# Sheet1.net
KiCad netlist of a schematic drawn in Altium Designer
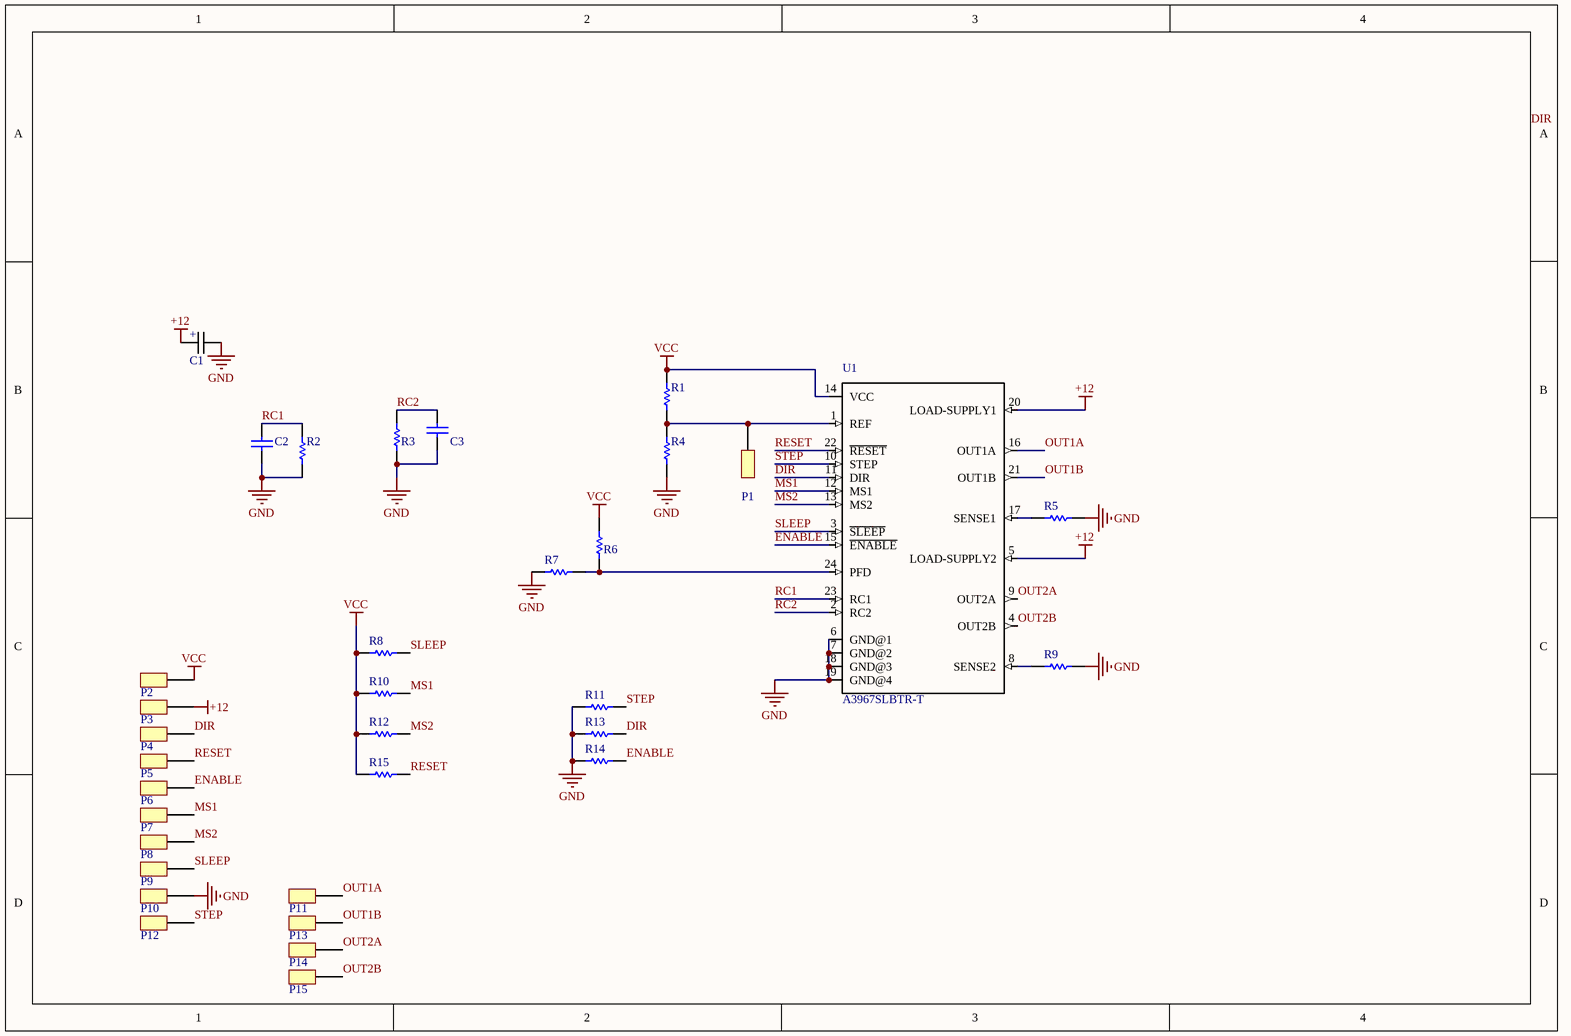
[diagram p0: Sheet1.SchDoc]

(export (version "E")
  (design (tool "Eeschema 10.0.6"))
  (components
    (comp (ref "C1") (value "~") (footprint "CAP 865080342006") (libsource (lib "SolarCar") (part "CAP")))
    (comp (ref "C2")
      (value "CAP 680pF 16V 0603(1608)")
      (footprint "CAPC0603(1608)100_M")
      (description "CAP 680pF 16V ±10% 0603 (1608 Metric) Thickness 1mm SMD")
      (fields (field (name "TOLERANCE") "Â±10%"))
      (libsource (lib "Altium Content Vault") (part "CAP"))
    )
    (comp (ref "C3")
      (value "CAP 680pF 16V 0603(1608)")
      (footprint "CAPC0603(1608)100_M")
      (description "CAP 680pF 16V ±10% 0603 (1608 Metric) Thickness 1mm SMD")
      (fields (field (name "TOLERANCE") "Â±10%"))
      (libsource (lib "Altium Content Vault") (part "CAP"))
    )
    (comp (ref "P1") (value "Pin 100mil") (footprint "Pin 100mil") (libsource (lib "") (part "1-Pin_1")))
    (comp (ref "P2")
      (value "Pin 100mil")
      (footprint "Pin 100mil")
      (libsource (lib "SolarCar") (part "1-Pin"))
    )
    (comp (ref "P3")
      (value "Pin 100mil")
      (footprint "Pin 100mil")
      (libsource (lib "SolarCar") (part "1-Pin"))
    )
    (comp (ref "P4")
      (value "Pin 100mil")
      (footprint "Pin 100mil")
      (libsource (lib "SolarCar") (part "1-Pin"))
    )
    (comp (ref "P5")
      (value "Pin 100mil")
      (footprint "Pin 100mil")
      (libsource (lib "SolarCar") (part "1-Pin"))
    )
    (comp (ref "P6")
      (value "Pin 100mil")
      (footprint "Pin 100mil")
      (libsource (lib "SolarCar") (part "1-Pin"))
    )
    (comp (ref "P7")
      (value "Pin 100mil")
      (footprint "Pin 100mil")
      (libsource (lib "SolarCar") (part "1-Pin"))
    )
    (comp (ref "P8")
      (value "Pin 100mil")
      (footprint "Pin 100mil")
      (libsource (lib "SolarCar") (part "1-Pin"))
    )
    (comp (ref "P9")
      (value "Pin 100mil")
      (footprint "Pin 100mil")
      (libsource (lib "SolarCar") (part "1-Pin"))
    )
    (comp (ref "P10")
      (value "Pin 100mil")
      (footprint "Pin 100mil")
      (libsource (lib "SolarCar") (part "1-Pin"))
    )
    (comp (ref "P11")
      (value "Pin 100mil")
      (footprint "Pin 100mil")
      (libsource (lib "SolarCar") (part "1-Pin"))
    )
    (comp (ref "P12")
      (value "Pin 100mil")
      (footprint "Pin 100mil")
      (libsource (lib "SolarCar") (part "1-Pin"))
    )
    (comp (ref "P13")
      (value "Pin 100mil")
      (footprint "Pin 100mil")
      (libsource (lib "SolarCar") (part "1-Pin"))
    )
    (comp (ref "P14")
      (value "Pin 100mil")
      (footprint "Pin 100mil")
      (libsource (lib "SolarCar") (part "1-Pin"))
    )
    (comp (ref "P15")
      (value "Pin 100mil")
      (footprint "Pin 100mil")
      (libsource (lib "SolarCar") (part "1-Pin"))
    )
    (comp (ref "R1")
      (value "6K04 1% 0603(1608)")
      (footprint "RESC0603(1608)_M")
      (description "6K04 0.1W 1% 0603 (1608 Metric)  SMD")
      (fields (field (name "TOLERANCE") "1 %") (field (name "POWER") "0.1 W"))
      (libsource (lib "Altium Content Vault") (part "RES"))
    )
    (comp (ref "R2")
      (value "20K 5% 0603(1608)")
      (footprint "RESC0603(1608)_N")
      (description "20K 0.1W 5% 0603 (1608 Metric)  SMD")
      (fields (field (name "TOLERANCE") "5 %") (field (name "POWER") "0.1 W"))
      (libsource (lib "Altium Content Vault") (part "RES"))
    )
    (comp (ref "R3")
      (value "20K 5% 0603(1608)")
      (footprint "RESC0603(1608)_N")
      (description "20K 0.1W 5% 0603 (1608 Metric)  SMD")
      (fields (field (name "TOLERANCE") "5 %") (field (name "POWER") "0.1 W"))
      (libsource (lib "Altium Content Vault") (part "RES"))
    )
    (comp (ref "R4")
      (value "4K02 1% 0603(1608)")
      (footprint "RESC0603(1608)_M")
      (description "4K02 0.1W 1% 0603 (1608 Metric)  SMD")
      (fields (field (name "TOLERANCE") "1 %") (field (name "POWER") "0.1 W"))
      (libsource (lib "Altium Content Vault") (part "RES"))
    )
    (comp (ref "R5")
      (value "Jumper 0603(1608)")
      (footprint "RESC0603(1608)_N")
      (description "Jumper 0603 (1608 Metric)")
      (fields (field (name "POWER") "None"))
      (libsource (lib "Altium Content Vault") (part "RES"))
    )
    (comp (ref "R6")
      (value "10K 1% 0603(1608)")
      (footprint "RESC0603(1608)_N")
      (description "10K 0.1W 1% 0603 (1608 Metric)  SMD")
      (fields (field (name "POWER") "0.1 W") (field (name "TOLERANCE") "1 %"))
      (libsource (lib "Altium Content Vault") (part "RES"))
    )
    (comp (ref "R7")
      (value "6K8 1% 0603(1608)")
      (footprint "RESC0603(1608)_M")
      (description "6K8 0.1W 1% 0603 (1608 Metric)  SMD")
      (fields (field (name "POWER") "0.1 W") (field (name "TOLERANCE") "1 %"))
      (libsource (lib "Altium Content Vault") (part "RES"))
    )
    (comp (ref "R8")
      (value "10K 1% 0603(1608)")
      (footprint "RESC0603(1608)_N")
      (description "10K 0.1W 1% 0603 (1608 Metric)  SMD")
      (fields (field (name "POWER") "0.1 W") (field (name "TOLERANCE") "1 %"))
      (libsource (lib "Altium Content Vault") (part "RES"))
    )
    (comp (ref "R9")
      (value "Jumper 0603(1608)")
      (footprint "RESC0603(1608)_N")
      (description "Jumper 0603 (1608 Metric)")
      (fields (field (name "POWER") "None"))
      (libsource (lib "Altium Content Vault") (part "RES"))
    )
    (comp (ref "R10")
      (value "10K 1% 0603(1608)")
      (footprint "RESC0603(1608)_N")
      (description "10K 0.1W 1% 0603 (1608 Metric)  SMD")
      (fields (field (name "POWER") "0.1 W") (field (name "TOLERANCE") "1 %"))
      (libsource (lib "Altium Content Vault") (part "RES"))
    )
    (comp (ref "R11")
      (value "10K 1% 0603(1608)")
      (footprint "RESC0603(1608)_N")
      (description "10K 0.1W 1% 0603 (1608 Metric)  SMD")
      (fields (field (name "POWER") "0.1 W") (field (name "TOLERANCE") "1 %"))
      (libsource (lib "Altium Content Vault") (part "RES"))
    )
    (comp (ref "R12")
      (value "10K 1% 0603(1608)")
      (footprint "RESC0603(1608)_N")
      (description "10K 0.1W 1% 0603 (1608 Metric)  SMD")
      (fields (field (name "POWER") "0.1 W") (field (name "TOLERANCE") "1 %"))
      (libsource (lib "Altium Content Vault") (part "RES"))
    )
    (comp (ref "R13")
      (value "10K 1% 0603(1608)")
      (footprint "RESC0603(1608)_N")
      (description "10K 0.1W 1% 0603 (1608 Metric)  SMD")
      (fields (field (name "POWER") "0.1 W") (field (name "TOLERANCE") "1 %"))
      (libsource (lib "Altium Content Vault") (part "RES"))
    )
    (comp (ref "R14")
      (value "10K 1% 0603(1608)")
      (footprint "RESC0603(1608)_N")
      (description "10K 0.1W 1% 0603 (1608 Metric)  SMD")
      (fields (field (name "POWER") "0.1 W") (field (name "TOLERANCE") "1 %"))
      (libsource (lib "Altium Content Vault") (part "RES"))
    )
    (comp (ref "R15")
      (value "10K 1% 0603(1608)")
      (footprint "RESC0603(1608)_N")
      (description "10K 0.1W 1% 0603 (1608 Metric)  SMD")
      (fields (field (name "POWER") "0.1 W") (field (name "TOLERANCE") "1 %"))
      (libsource (lib "Altium Content Vault") (part "RES"))
    )
    (comp (ref "U1")
      (value "A3967SLBTR-T")
      (footprint "*SOIC24WIDE")
      (description "Ic Motor Driver Pwm Full 24soic - A3967slbtr-t")
      (fields (field (name "DIGI-KEY_PART_NUMBER") "620-1140-1-ND") (field (name "MF") "Allegro"))
      (libsource (lib "A3967SLBTR-T") (part "A3967SLBTR-T"))
    )
  )
  (nets
    (net (code "1") (name "+12") (class "Default")
      (node (ref "C1") (pin "+") (pinfunction "+_+") (pintype "power_in"))
      (node (ref "P3") (pin "0") (pinfunction "0_0") (pintype "passive"))
      (node (ref "U1") (pin "20") (pinfunction "LOAD-SUPPLY1_20") (pintype "input"))
      (node (ref "U1") (pin "5") (pinfunction "LOAD-SUPPLY2_5") (pintype "input"))
    )
    (net (code "2") (name "/DIR") (class "Default")
      (node (ref "P4") (pin "0") (pinfunction "0_0") (pintype "passive"))
      (node (ref "R13") (pin "2") (pinfunction "2_2") (pintype "passive"))
      (node (ref "U1") (pin "11") (pinfunction "DIR_11") (pintype "input"))
    )
    (net (code "3") (name "/ENABLE") (class "Default")
      (node (ref "P6") (pin "0") (pinfunction "0_0") (pintype "passive"))
      (node (ref "R14") (pin "2") (pinfunction "2_2") (pintype "passive"))
      (node (ref "U1") (pin "15") (pinfunction "~{ENABLE}_15") (pintype "input"))
    )
    (net (code "4") (name "/MS1") (class "Default")
      (node (ref "P7") (pin "0") (pinfunction "0_0") (pintype "passive"))
      (node (ref "R10") (pin "2") (pinfunction "2_2") (pintype "passive"))
      (node (ref "U1") (pin "12") (pinfunction "MS1_12") (pintype "input"))
    )
    (net (code "5") (name "/MS2") (class "Default")
      (node (ref "P8") (pin "0") (pinfunction "0_0") (pintype "passive"))
      (node (ref "R12") (pin "2") (pinfunction "2_2") (pintype "passive"))
      (node (ref "U1") (pin "13") (pinfunction "MS2_13") (pintype "input"))
    )
    (net (code "6") (name "/OUT1A") (class "Default")
      (node (ref "P11") (pin "0") (pinfunction "0_0") (pintype "passive"))
      (node (ref "U1") (pin "16") (pinfunction "OUT1A_16") (pintype "output"))
    )
    (net (code "7") (name "/OUT1B") (class "Default")
      (node (ref "P13") (pin "0") (pinfunction "0_0") (pintype "passive"))
      (node (ref "U1") (pin "21") (pinfunction "OUT1B_21") (pintype "output"))
    )
    (net (code "8") (name "/OUT2A") (class "Default")
      (node (ref "P14") (pin "0") (pinfunction "0_0") (pintype "passive"))
      (node (ref "U1") (pin "9") (pinfunction "OUT2A_9") (pintype "output"))
    )
    (net (code "9") (name "/OUT2B") (class "Default")
      (node (ref "P15") (pin "0") (pinfunction "0_0") (pintype "passive"))
      (node (ref "U1") (pin "4") (pinfunction "OUT2B_4") (pintype "output"))
    )
    (net (code "10") (name "/RC1") (class "Default")
      (node (ref "C2") (pin "2") (pinfunction "2_2") (pintype "passive"))
      (node (ref "R2") (pin "2") (pinfunction "2_2") (pintype "passive"))
      (node (ref "U1") (pin "23") (pinfunction "RC1_23") (pintype "input"))
    )
    (net (code "11") (name "/RC2") (class "Default")
      (node (ref "C3") (pin "2") (pinfunction "2_2") (pintype "passive"))
      (node (ref "R3") (pin "2") (pinfunction "2_2") (pintype "passive"))
      (node (ref "U1") (pin "2") (pinfunction "RC2_2") (pintype "input"))
    )
    (net (code "12") (name "/RESET") (class "Default")
      (node (ref "P5") (pin "0") (pinfunction "0_0") (pintype "passive"))
      (node (ref "R15") (pin "2") (pinfunction "2_2") (pintype "passive"))
      (node (ref "U1") (pin "22") (pinfunction "~{RESET}_22") (pintype "input"))
    )
    (net (code "13") (name "/SLEEP") (class "Default")
      (node (ref "P9") (pin "0") (pinfunction "0_0") (pintype "passive"))
      (node (ref "R8") (pin "2") (pinfunction "2_2") (pintype "passive"))
      (node (ref "U1") (pin "3") (pinfunction "~{SLEEP}_3") (pintype "input"))
    )
    (net (code "14") (name "/STEP") (class "Default")
      (node (ref "P12") (pin "0") (pinfunction "0_0") (pintype "passive"))
      (node (ref "R11") (pin "2") (pinfunction "2_2") (pintype "passive"))
      (node (ref "U1") (pin "10") (pinfunction "STEP_10") (pintype "input"))
    )
    (net (code "15") (name "GND") (class "Default")
      (node (ref "C1") (pin "-") (pinfunction "-_-") (pintype "power_in"))
      (node (ref "C2") (pin "1") (pinfunction "1_1") (pintype "passive"))
      (node (ref "C3") (pin "1") (pinfunction "1_1") (pintype "passive"))
      (node (ref "P10") (pin "0") (pinfunction "0_0") (pintype "passive"))
      (node (ref "R11") (pin "1") (pinfunction "1_1") (pintype "passive"))
      (node (ref "R13") (pin "1") (pinfunction "1_1") (pintype "passive"))
      (node (ref "R14") (pin "1") (pinfunction "1_1") (pintype "passive"))
      (node (ref "R2") (pin "1") (pinfunction "1_1") (pintype "passive"))
      (node (ref "R3") (pin "1") (pinfunction "1_1") (pintype "passive"))
      (node (ref "R4") (pin "1") (pinfunction "1_1") (pintype "passive"))
      (node (ref "R5") (pin "2") (pinfunction "2_2") (pintype "passive"))
      (node (ref "R7") (pin "1") (pinfunction "1_1") (pintype "passive"))
      (node (ref "R9") (pin "2") (pinfunction "2_2") (pintype "passive"))
      (node (ref "U1") (pin "18") (pinfunction "GND@3_18") (pintype "power_in"))
      (node (ref "U1") (pin "19") (pinfunction "GND@4_19") (pintype "power_in"))
      (node (ref "U1") (pin "6") (pinfunction "GND@1_6") (pintype "power_in"))
      (node (ref "U1") (pin "7") (pinfunction "GND@2_7") (pintype "power_in"))
    )
    (net (code "16") (name "Net-(U1-PFD)") (class "Default")
      (node (ref "R6") (pin "1") (pinfunction "1_1") (pintype "passive"))
      (node (ref "R7") (pin "2") (pinfunction "2_2") (pintype "passive"))
      (node (ref "U1") (pin "24") (pinfunction "PFD_24") (pintype "input"))
    )
    (net (code "17") (name "Net-(U1-REF)") (class "Default")
      (node (ref "P1") (pin "0") (pinfunction "0_0") (pintype "passive"))
      (node (ref "R1") (pin "1") (pinfunction "1_1") (pintype "passive"))
      (node (ref "R4") (pin "2") (pinfunction "2_2") (pintype "passive"))
      (node (ref "U1") (pin "1") (pinfunction "REF_1") (pintype "input"))
    )
    (net (code "18") (name "Net-(U1-SENSE1)") (class "Default")
      (node (ref "R5") (pin "1") (pinfunction "1_1") (pintype "passive"))
      (node (ref "U1") (pin "17") (pinfunction "SENSE1_17") (pintype "input"))
    )
    (net (code "19") (name "Net-(U1-SENSE2)") (class "Default")
      (node (ref "R9") (pin "1") (pinfunction "1_1") (pintype "passive"))
      (node (ref "U1") (pin "8") (pinfunction "SENSE2_8") (pintype "input"))
    )
    (net (code "20") (name "VCC") (class "Default")
      (node (ref "P2") (pin "0") (pinfunction "0_0") (pintype "passive"))
      (node (ref "R1") (pin "2") (pinfunction "2_2") (pintype "passive"))
      (node (ref "R10") (pin "1") (pinfunction "1_1") (pintype "passive"))
      (node (ref "R12") (pin "1") (pinfunction "1_1") (pintype "passive"))
      (node (ref "R15") (pin "1") (pinfunction "1_1") (pintype "passive"))
      (node (ref "R6") (pin "2") (pinfunction "2_2") (pintype "passive"))
      (node (ref "R8") (pin "1") (pinfunction "1_1") (pintype "passive"))
      (node (ref "U1") (pin "14") (pinfunction "VCC_14") (pintype "power_in"))
    )
  )
)
